# Sheet1.net
KiCad netlist of a schematic drawn in Altium Designer
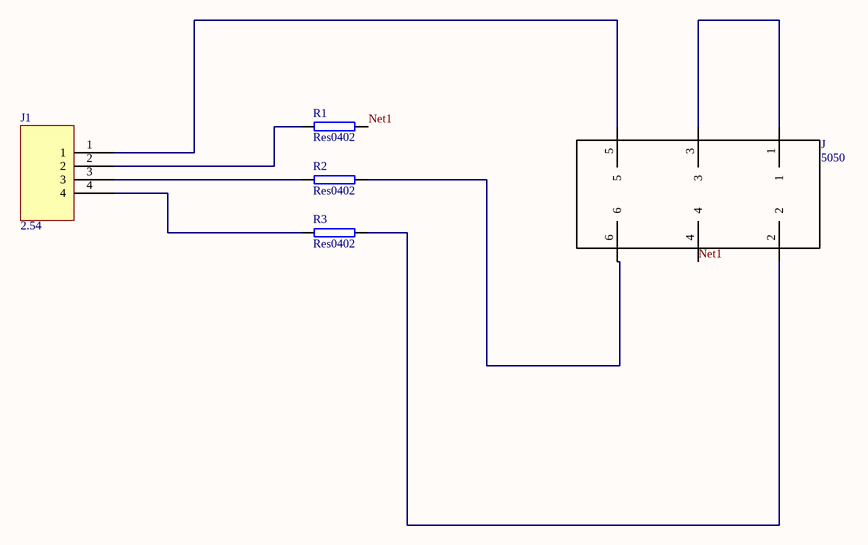
[diagram p0: Sheet1.SchDoc]

(export (version "E")
  (design (tool "Eeschema 10.0.6"))
  (components
    (comp (ref "J") (value "5050") (footprint "5050") (libsource (lib "zhangchong") (part "5050")))
    (comp (ref "J1") (value "2.54") (footprint "pz-2.54") (libsource (lib "zhangchong") (part "2.54")))
    (comp (ref "R1") (value "Res0402") (footprint "0402") (libsource (lib "gupeng_sch") (part "Res0402")))
    (comp (ref "R2") (value "Res0402") (footprint "0402") (libsource (lib "gupeng_sch") (part "Res0402")))
    (comp (ref "R3") (value "Res0402") (footprint "0402") (libsource (lib "gupeng_sch") (part "Res0402")))
  )
  (nets
    (net (code "1") (name "/Net1") (class "Default")
      (node (ref "J") (pin "4") (pinfunction "4_4") (pintype "passive"))
      (node (ref "R1") (pin "2") (pinfunction "2_2") (pintype "passive"))
    )
    (net (code "2") (name "Net-(J-Pad1)") (class "Default")
      (node (ref "J") (pin "1") (pinfunction "1_1") (pintype "passive"))
      (node (ref "J") (pin "3") (pinfunction "3_3") (pintype "passive"))
    )
    (net (code "3") (name "Net-(J-Pad2)") (class "Default")
      (node (ref "J") (pin "2") (pinfunction "2_2") (pintype "passive"))
      (node (ref "R3") (pin "2") (pinfunction "2_2") (pintype "passive"))
    )
    (net (code "4") (name "Net-(J-Pad5)") (class "Default")
      (node (ref "J") (pin "5") (pinfunction "5_5") (pintype "passive"))
      (node (ref "J1") (pin "1") (pinfunction "1_1") (pintype "passive"))
    )
    (net (code "5") (name "Net-(J-Pad6)") (class "Default")
      (node (ref "J") (pin "6") (pinfunction "6_6") (pintype "passive"))
      (node (ref "R2") (pin "2") (pinfunction "2_2") (pintype "passive"))
    )
    (net (code "6") (name "Net-(J1-Pad2)") (class "Default")
      (node (ref "J1") (pin "2") (pinfunction "2_2") (pintype "passive"))
      (node (ref "R1") (pin "1") (pinfunction "1_1") (pintype "passive"))
    )
    (net (code "7") (name "Net-(J1-Pad3)") (class "Default")
      (node (ref "J1") (pin "3") (pinfunction "3_3") (pintype "passive"))
      (node (ref "R2") (pin "1") (pinfunction "1_1") (pintype "passive"))
    )
    (net (code "8") (name "Net-(J1-Pad4)") (class "Default")
      (node (ref "J1") (pin "4") (pinfunction "4_4") (pintype "passive"))
      (node (ref "R3") (pin "1") (pinfunction "1_1") (pintype "passive"))
    )
  )
)
